# SNES_DRONE_GPIO.net
KiCad netlist of a schematic drawn in Altium Designer
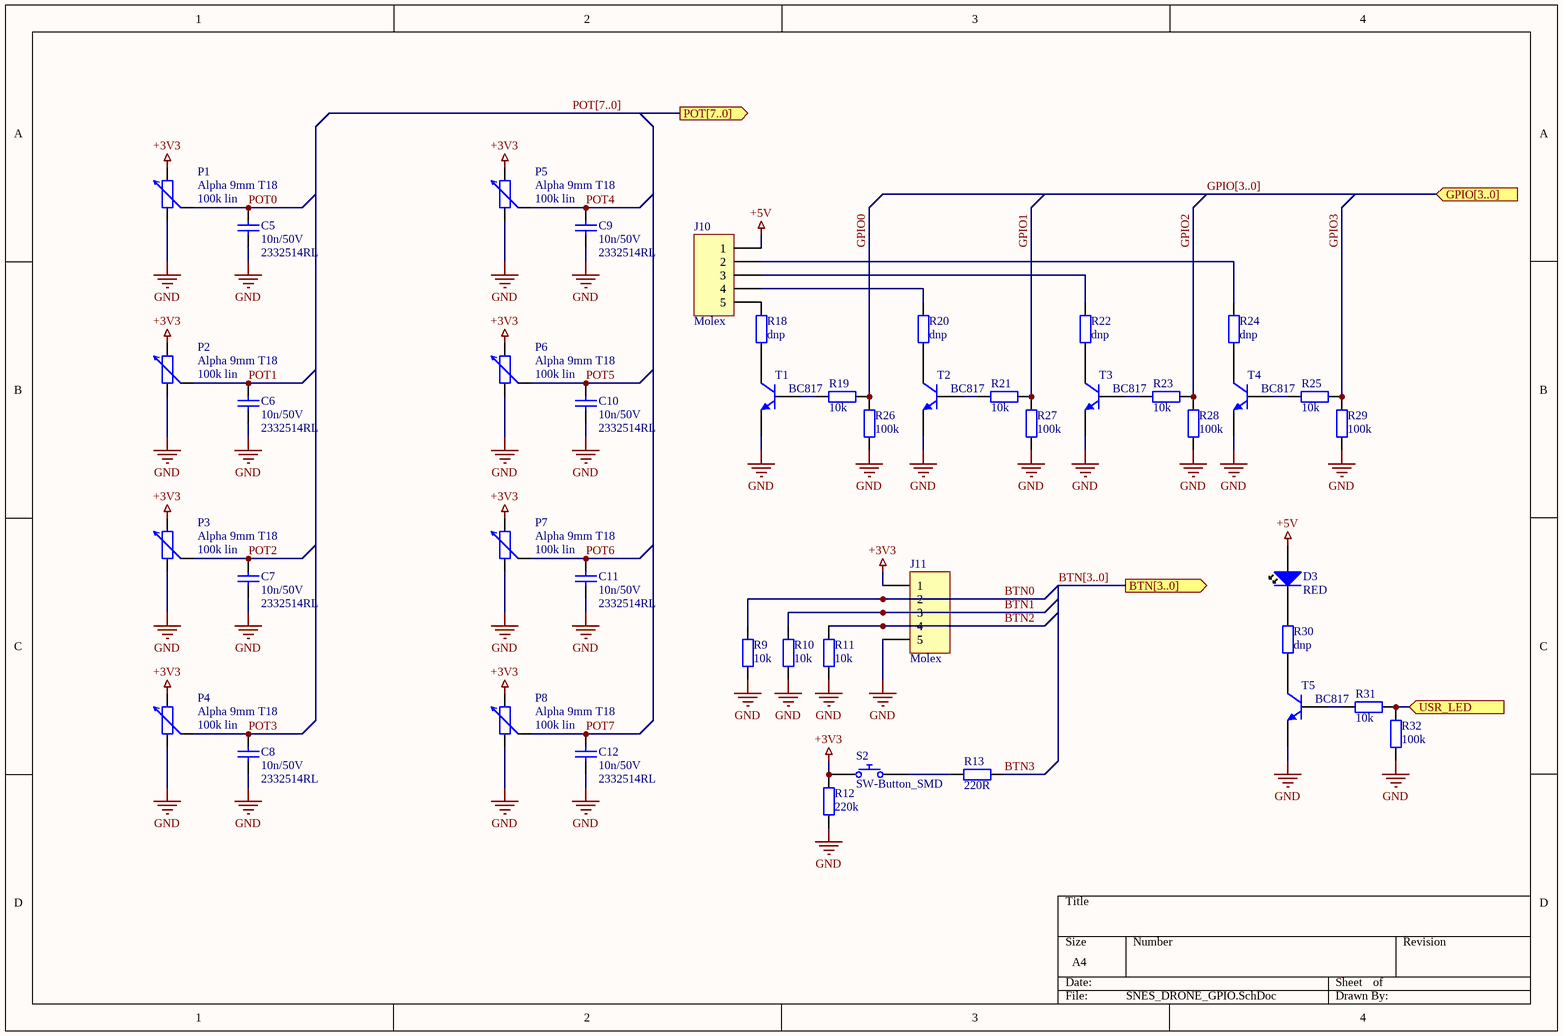
[diagram p0: SNES_DRONE_GPIO.SchDoc]

(export (version "E")
  (design (tool "Eeschema 10.0.6"))
  (components
    (comp (ref "C5")
      (value "10n/50V")
      (footprint "0402_RES")
      (fields (field (name "SUPPLIER PART NUMBER 1") "2332514RL"))
      (libsource (lib "My_Integrated_Library") (part "Cap_10n_0402"))
    )
    (comp (ref "C6")
      (value "10n/50V")
      (footprint "0402_RES")
      (fields (field (name "SUPPLIER PART NUMBER 1") "2332514RL"))
      (libsource (lib "My_Integrated_Library") (part "Cap_10n_0402"))
    )
    (comp (ref "C7")
      (value "10n/50V")
      (footprint "0402_RES")
      (fields (field (name "SUPPLIER PART NUMBER 1") "2332514RL"))
      (libsource (lib "My_Integrated_Library") (part "Cap_10n_0402"))
    )
    (comp (ref "C8")
      (value "10n/50V")
      (footprint "0402_RES")
      (fields (field (name "SUPPLIER PART NUMBER 1") "2332514RL"))
      (libsource (lib "My_Integrated_Library") (part "Cap_10n_0402"))
    )
    (comp (ref "C9")
      (value "10n/50V")
      (footprint "0402_RES")
      (fields (field (name "SUPPLIER PART NUMBER 1") "2332514RL"))
      (libsource (lib "My_Integrated_Library") (part "Cap_10n_0402"))
    )
    (comp (ref "C10")
      (value "10n/50V")
      (footprint "0402_RES")
      (fields (field (name "SUPPLIER PART NUMBER 1") "2332514RL"))
      (libsource (lib "My_Integrated_Library") (part "Cap_10n_0402"))
    )
    (comp (ref "C11")
      (value "10n/50V")
      (footprint "0402_RES")
      (fields (field (name "SUPPLIER PART NUMBER 1") "2332514RL"))
      (libsource (lib "My_Integrated_Library") (part "Cap_10n_0402"))
    )
    (comp (ref "C12")
      (value "10n/50V")
      (footprint "0402_RES")
      (fields (field (name "SUPPLIER PART NUMBER 1") "2332514RL"))
      (libsource (lib "My_Integrated_Library") (part "Cap_10n_0402"))
    )
    (comp (ref "D3")
      (value "RED")
      (footprint "0603_LED")
      (description "RED SMD 0603 LED 20mA 2V 0.04W")
      (fields (field (name "Comment") "RED LED"))
      (libsource (lib "My_Integrated_Library") (part "LED_RED_0603"))
    )
    (comp (ref "J10")
      (value "MOLEX_22-27-2051")
      (footprint "MOLEX_22-27-2051")
      (description "5 pin molex connector")
      (fields (field (name "MANUFACTURER 1") "Molex"))
      (libsource (lib "") (part "MOLEX_22-27-2051_1"))
    )
    (comp (ref "J11")
      (value "MOLEX_22-27-2051")
      (footprint "MOLEX_22-27-2051")
      (description "5 pin molex connector")
      (fields (field (name "MANUFACTURER 1") "Molex"))
      (libsource (lib "My_Integrated_Library") (part "MOLEX_22-27-2051"))
    )
    (comp (ref "P1")
      (value "100k lin")
      (footprint "ALPHA_T18")
      (description "Shaft Diameter – 6mm (0.2″)\r\nShaft Length – 15mm (0.59″)")
      (fields (field (name "NAME") "Alpha 9mm T18") (field (name "Comment") "RES_POT_100k_LIN_ALPHA_EURACK"))
      (libsource (lib "My_Integrated_Library") (part "RES_POT_100k_LIN_ALPHA_EURACK"))
    )
    (comp (ref "P2")
      (value "100k lin")
      (footprint "ALPHA_T18")
      (description "Shaft Diameter – 6mm (0.2″)\r\nShaft Length – 15mm (0.59″)")
      (fields (field (name "NAME") "Alpha 9mm T18") (field (name "Comment") "RES_POT_100k_LIN_ALPHA_EURACK"))
      (libsource (lib "My_Integrated_Library") (part "RES_POT_100k_LIN_ALPHA_EURACK"))
    )
    (comp (ref "P3")
      (value "100k lin")
      (footprint "ALPHA_T18")
      (description "Shaft Diameter – 6mm (0.2″)\r\nShaft Length – 15mm (0.59″)")
      (fields (field (name "NAME") "Alpha 9mm T18") (field (name "Comment") "RES_POT_100k_LIN_ALPHA_EURACK"))
      (libsource (lib "My_Integrated_Library") (part "RES_POT_100k_LIN_ALPHA_EURACK"))
    )
    (comp (ref "P4")
      (value "100k lin")
      (footprint "ALPHA_T18")
      (description "Shaft Diameter – 6mm (0.2″)\r\nShaft Length – 15mm (0.59″)")
      (fields (field (name "NAME") "Alpha 9mm T18") (field (name "Comment") "RES_POT_100k_LIN_ALPHA_EURACK"))
      (libsource (lib "My_Integrated_Library") (part "RES_POT_100k_LIN_ALPHA_EURACK"))
    )
    (comp (ref "P5")
      (value "100k lin")
      (footprint "ALPHA_T18")
      (description "Shaft Diameter – 6mm (0.2″)\r\nShaft Length – 15mm (0.59″)")
      (fields (field (name "NAME") "Alpha 9mm T18") (field (name "Comment") "RES_POT_100k_LIN_ALPHA_EURACK"))
      (libsource (lib "My_Integrated_Library") (part "RES_POT_100k_LIN_ALPHA_EURACK"))
    )
    (comp (ref "P6")
      (value "100k lin")
      (footprint "ALPHA_T18")
      (description "Shaft Diameter – 6mm (0.2″)\r\nShaft Length – 15mm (0.59″)")
      (fields (field (name "NAME") "Alpha 9mm T18") (field (name "Comment") "RES_POT_100k_LIN_ALPHA_EURACK"))
      (libsource (lib "My_Integrated_Library") (part "RES_POT_100k_LIN_ALPHA_EURACK"))
    )
    (comp (ref "P7")
      (value "100k lin")
      (footprint "ALPHA_T18")
      (description "Shaft Diameter – 6mm (0.2″)\r\nShaft Length – 15mm (0.59″)")
      (fields (field (name "NAME") "Alpha 9mm T18") (field (name "Comment") "RES_POT_100k_LIN_ALPHA_EURACK"))
      (libsource (lib "My_Integrated_Library") (part "RES_POT_100k_LIN_ALPHA_EURACK"))
    )
    (comp (ref "P8")
      (value "100k lin")
      (footprint "ALPHA_T18")
      (description "Shaft Diameter – 6mm (0.2″)\r\nShaft Length – 15mm (0.59″)")
      (fields (field (name "NAME") "Alpha 9mm T18") (field (name "Comment") "RES_POT_100k_LIN_ALPHA_EURACK"))
      (libsource (lib "My_Integrated_Library") (part "RES_POT_100k_LIN_ALPHA_EURACK"))
    )
    (comp (ref "R9")
      (value "10k")
      (footprint "0603_RES")
      (description "YAGEO 10kOhm 100mW ± 1%")
      (fields (field (name "Comment") "10kOhm 100mW"))
      (libsource (lib "My_Integrated_Library") (part "RES_0603_10k_100mW"))
    )
    (comp (ref "R10")
      (value "10k")
      (footprint "0603_RES")
      (description "YAGEO 10kOhm 100mW ± 1%")
      (fields (field (name "Comment") "10kOhm 100mW"))
      (libsource (lib "My_Integrated_Library") (part "RES_0603_10k_100mW"))
    )
    (comp (ref "R11")
      (value "10k")
      (footprint "0603_RES")
      (description "YAGEO 10kOhm 100mW ± 1%")
      (fields (field (name "Comment") "10kOhm 100mW"))
      (libsource (lib "My_Integrated_Library") (part "RES_0603_10k_100mW"))
    )
    (comp (ref "R12")
      (value "220k")
      (footprint "0603_RES")
      (description "VISHAY 220kOhm 100mW ± 1%")
      (fields (field (name "Comment") "220kOhm 100mW"))
      (libsource (lib "My_Integrated_Library") (part "RES_0603_220k_100mW"))
    )
    (comp (ref "R13")
      (value "220R")
      (footprint "0603_RES")
      (description "YAGEO 220Ohm 100mW ± 1%")
      (fields (field (name "Comment") "220Ohm 100mW"))
      (libsource (lib "My_Integrated_Library") (part "RES_0603_220_100mW"))
    )
    (comp (ref "R18")
      (value "dnp")
      (footprint "0603_DNP")
      (fields (field (name "Comment") "DNP"))
      (libsource (lib "My_Integrated_Library") (part "RES_DNP"))
    )
    (comp (ref "R19")
      (value "10k")
      (footprint "0603_RES")
      (description "YAGEO 10kOhm 100mW ± 1%")
      (fields (field (name "Comment") "10kOhm 100mW"))
      (libsource (lib "") (part "RES_0603_10k_100mW_1"))
    )
    (comp (ref "R20")
      (value "dnp")
      (footprint "0603_DNP")
      (fields (field (name "Comment") "DNP"))
      (libsource (lib "My_Integrated_Library") (part "RES_DNP"))
    )
    (comp (ref "R21")
      (value "10k")
      (footprint "0603_RES")
      (description "YAGEO 10kOhm 100mW ± 1%")
      (fields (field (name "Comment") "10kOhm 100mW"))
      (libsource (lib "") (part "RES_0603_10k_100mW_1"))
    )
    (comp (ref "R22")
      (value "dnp")
      (footprint "0603_DNP")
      (fields (field (name "Comment") "DNP"))
      (libsource (lib "My_Integrated_Library") (part "RES_DNP"))
    )
    (comp (ref "R23")
      (value "10k")
      (footprint "0603_RES")
      (description "YAGEO 10kOhm 100mW ± 1%")
      (fields (field (name "Comment") "10kOhm 100mW"))
      (libsource (lib "") (part "RES_0603_10k_100mW_1"))
    )
    (comp (ref "R24")
      (value "dnp")
      (footprint "0603_DNP")
      (fields (field (name "Comment") "DNP"))
      (libsource (lib "My_Integrated_Library") (part "RES_DNP"))
    )
    (comp (ref "R25")
      (value "10k")
      (footprint "0603_RES")
      (description "YAGEO 10kOhm 100mW ± 1%")
      (fields (field (name "Comment") "10kOhm 100mW"))
      (libsource (lib "") (part "RES_0603_10k_100mW_1"))
    )
    (comp (ref "R26")
      (value "100k")
      (footprint "0603_RES")
      (description "WALSIN 6.8kOhm 100mW 75 ± 1%")
      (fields (field (name "Comment") "100kOhm 100mW"))
      (libsource (lib "My_Integrated_Library") (part "RES_0603_100k_100mW"))
    )
    (comp (ref "R27")
      (value "100k")
      (footprint "0603_RES")
      (description "WALSIN 6.8kOhm 100mW 75 ± 1%")
      (fields (field (name "Comment") "100kOhm 100mW"))
      (libsource (lib "My_Integrated_Library") (part "RES_0603_100k_100mW"))
    )
    (comp (ref "R28")
      (value "100k")
      (footprint "0603_RES")
      (description "WALSIN 6.8kOhm 100mW 75 ± 1%")
      (fields (field (name "Comment") "100kOhm 100mW"))
      (libsource (lib "My_Integrated_Library") (part "RES_0603_100k_100mW"))
    )
    (comp (ref "R29")
      (value "100k")
      (footprint "0603_RES")
      (description "WALSIN 6.8kOhm 100mW 75 ± 1%")
      (fields (field (name "Comment") "100kOhm 100mW"))
      (libsource (lib "My_Integrated_Library") (part "RES_0603_100k_100mW"))
    )
    (comp (ref "R30")
      (value "dnp")
      (footprint "0603_DNP")
      (fields (field (name "Comment") "DNP"))
      (libsource (lib "My_Integrated_Library") (part "RES_DNP"))
    )
    (comp (ref "R31")
      (value "10k")
      (footprint "0603_RES")
      (description "YAGEO 10kOhm 100mW ± 1%")
      (fields (field (name "Comment") "10kOhm 100mW"))
      (libsource (lib "") (part "RES_0603_10k_100mW_1"))
    )
    (comp (ref "R32")
      (value "100k")
      (footprint "0603_RES")
      (description "WALSIN 6.8kOhm 100mW 75 ± 1%")
      (fields (field (name "Comment") "100kOhm 100mW"))
      (libsource (lib "My_Integrated_Library") (part "RES_0603_100k_100mW"))
    )
    (comp (ref "S2")
      (value "SW-Button_SMD")
      (footprint "SKQGAFE010")
      (description "ALPS SMD Push Button")
      (libsource (lib "My_Integrated_Library") (part "SW-Button_SMD"))
    )
    (comp (ref "T1")
      (value "BC817")
      (footprint "TO-236AB")
      (description "BJT, NPN, 45 V, 250 mW, 500 mA, 160 hFE")
      (libsource (lib "My_Integrated_Library") (part "BJT_NPN_BC817"))
    )
    (comp (ref "T2")
      (value "BC817")
      (footprint "TO-236AB")
      (description "BJT, NPN, 45 V, 250 mW, 500 mA, 160 hFE")
      (libsource (lib "My_Integrated_Library") (part "BJT_NPN_BC817"))
    )
    (comp (ref "T3")
      (value "BC817")
      (footprint "TO-236AB")
      (description "BJT, NPN, 45 V, 250 mW, 500 mA, 160 hFE")
      (libsource (lib "My_Integrated_Library") (part "BJT_NPN_BC817"))
    )
    (comp (ref "T4")
      (value "BC817")
      (footprint "TO-236AB")
      (description "BJT, NPN, 45 V, 250 mW, 500 mA, 160 hFE")
      (libsource (lib "My_Integrated_Library") (part "BJT_NPN_BC817"))
    )
    (comp (ref "T5")
      (value "BC817")
      (footprint "TO-236AB")
      (description "BJT, NPN, 45 V, 250 mW, 500 mA, 160 hFE")
      (libsource (lib "My_Integrated_Library") (part "BJT_NPN_BC817"))
    )
  )
  (nets
    (net (code "1") (name "+3V3") (class "Default")
      (node (ref "J11") (pin "1") (pinfunction "1_1") (pintype "passive"))
      (node (ref "P1") (pin "1") (pinfunction "1_1") (pintype "passive"))
      (node (ref "P2") (pin "1") (pinfunction "1_1") (pintype "passive"))
      (node (ref "P3") (pin "1") (pinfunction "1_1") (pintype "passive"))
      (node (ref "P4") (pin "1") (pinfunction "1_1") (pintype "passive"))
      (node (ref "P5") (pin "1") (pinfunction "1_1") (pintype "passive"))
      (node (ref "P6") (pin "1") (pinfunction "1_1") (pintype "passive"))
      (node (ref "P7") (pin "1") (pinfunction "1_1") (pintype "passive"))
      (node (ref "P8") (pin "1") (pinfunction "1_1") (pintype "passive"))
      (node (ref "R12") (pin "2") (pinfunction "2_2") (pintype "passive"))
      (node (ref "S2") (pin "3") (pinfunction "3_3") (pintype "passive"))
    )
    (net (code "2") (name "+5V") (class "Default")
      (node (ref "D3") (pin "1") (pinfunction "A_1") (pintype "passive"))
      (node (ref "J10") (pin "1") (pinfunction "1_1") (pintype "passive"))
    )
    (net (code "3") (name "/BTN0") (class "Default")
      (node (ref "J11") (pin "2") (pinfunction "2_2") (pintype "passive"))
      (node (ref "R9") (pin "2") (pinfunction "2_2") (pintype "passive"))
    )
    (net (code "4") (name "/BTN1") (class "Default")
      (node (ref "J11") (pin "3") (pinfunction "3_3") (pintype "passive"))
      (node (ref "R10") (pin "2") (pinfunction "2_2") (pintype "passive"))
    )
    (net (code "5") (name "/BTN2") (class "Default")
      (node (ref "J11") (pin "4") (pinfunction "4_4") (pintype "passive"))
      (node (ref "R11") (pin "2") (pinfunction "2_2") (pintype "passive"))
    )
    (net (code "6") (name "/BTN3") (class "Default")
      (node (ref "R13") (pin "2") (pinfunction "2_2") (pintype "passive"))
    )
    (net (code "8") (name "/GPIO0") (class "Default")
      (node (ref "R19") (pin "1") (pinfunction "1_1") (pintype "passive"))
      (node (ref "R26") (pin "2") (pinfunction "2_2") (pintype "passive"))
    )
    (net (code "9") (name "/GPIO1") (class "Default")
      (node (ref "R21") (pin "1") (pinfunction "1_1") (pintype "passive"))
      (node (ref "R27") (pin "2") (pinfunction "2_2") (pintype "passive"))
    )
    (net (code "10") (name "/GPIO2") (class "Default")
      (node (ref "R23") (pin "1") (pinfunction "1_1") (pintype "passive"))
      (node (ref "R28") (pin "2") (pinfunction "2_2") (pintype "passive"))
    )
    (net (code "11") (name "/GPIO3") (class "Default")
      (node (ref "R25") (pin "1") (pinfunction "1_1") (pintype "passive"))
      (node (ref "R29") (pin "2") (pinfunction "2_2") (pintype "passive"))
    )
    (net (code "13") (name "/POT0") (class "Default")
      (node (ref "C5") (pin "2") (pinfunction "2_2") (pintype "passive"))
      (node (ref "P1") (pin "2") (pinfunction "2_2") (pintype "passive"))
    )
    (net (code "14") (name "/POT1") (class "Default")
      (node (ref "C6") (pin "2") (pinfunction "2_2") (pintype "passive"))
      (node (ref "P2") (pin "2") (pinfunction "2_2") (pintype "passive"))
    )
    (net (code "15") (name "/POT2") (class "Default")
      (node (ref "C7") (pin "2") (pinfunction "2_2") (pintype "passive"))
      (node (ref "P3") (pin "2") (pinfunction "2_2") (pintype "passive"))
    )
    (net (code "16") (name "/POT3") (class "Default")
      (node (ref "C8") (pin "2") (pinfunction "2_2") (pintype "passive"))
      (node (ref "P4") (pin "2") (pinfunction "2_2") (pintype "passive"))
    )
    (net (code "17") (name "/POT4") (class "Default")
      (node (ref "C9") (pin "2") (pinfunction "2_2") (pintype "passive"))
      (node (ref "P5") (pin "2") (pinfunction "2_2") (pintype "passive"))
    )
    (net (code "18") (name "/POT5") (class "Default")
      (node (ref "C10") (pin "2") (pinfunction "2_2") (pintype "passive"))
      (node (ref "P6") (pin "2") (pinfunction "2_2") (pintype "passive"))
    )
    (net (code "19") (name "/POT6") (class "Default")
      (node (ref "C11") (pin "2") (pinfunction "2_2") (pintype "passive"))
      (node (ref "P7") (pin "2") (pinfunction "2_2") (pintype "passive"))
    )
    (net (code "20") (name "/POT7") (class "Default")
      (node (ref "C12") (pin "2") (pinfunction "2_2") (pintype "passive"))
      (node (ref "P8") (pin "2") (pinfunction "2_2") (pintype "passive"))
    )
    (net (code "22") (name "/USR_LED") (class "Default")
      (node (ref "R31") (pin "1") (pinfunction "1_1") (pintype "passive"))
      (node (ref "R32") (pin "2") (pinfunction "2_2") (pintype "passive"))
    )
    (net (code "23") (name "GND") (class "Default")
      (node (ref "C10") (pin "1") (pinfunction "1_1") (pintype "passive"))
      (node (ref "C11") (pin "1") (pinfunction "1_1") (pintype "passive"))
      (node (ref "C12") (pin "1") (pinfunction "1_1") (pintype "passive"))
      (node (ref "C5") (pin "1") (pinfunction "1_1") (pintype "passive"))
      (node (ref "C6") (pin "1") (pinfunction "1_1") (pintype "passive"))
      (node (ref "C7") (pin "1") (pinfunction "1_1") (pintype "passive"))
      (node (ref "C8") (pin "1") (pinfunction "1_1") (pintype "passive"))
      (node (ref "C9") (pin "1") (pinfunction "1_1") (pintype "passive"))
      (node (ref "J11") (pin "5") (pinfunction "5_5") (pintype "passive"))
      (node (ref "P1") (pin "3") (pinfunction "3_3") (pintype "passive"))
      (node (ref "P2") (pin "3") (pinfunction "3_3") (pintype "passive"))
      (node (ref "P3") (pin "3") (pinfunction "3_3") (pintype "passive"))
      (node (ref "P4") (pin "3") (pinfunction "3_3") (pintype "passive"))
      (node (ref "P5") (pin "3") (pinfunction "3_3") (pintype "passive"))
      (node (ref "P6") (pin "3") (pinfunction "3_3") (pintype "passive"))
      (node (ref "P7") (pin "3") (pinfunction "3_3") (pintype "passive"))
      (node (ref "P8") (pin "3") (pinfunction "3_3") (pintype "passive"))
      (node (ref "R10") (pin "1") (pinfunction "1_1") (pintype "passive"))
      (node (ref "R11") (pin "1") (pinfunction "1_1") (pintype "passive"))
      (node (ref "R12") (pin "1") (pinfunction "1_1") (pintype "passive"))
      (node (ref "R26") (pin "1") (pinfunction "1_1") (pintype "passive"))
      (node (ref "R27") (pin "1") (pinfunction "1_1") (pintype "passive"))
      (node (ref "R28") (pin "1") (pinfunction "1_1") (pintype "passive"))
      (node (ref "R29") (pin "1") (pinfunction "1_1") (pintype "passive"))
      (node (ref "R32") (pin "1") (pinfunction "1_1") (pintype "passive"))
      (node (ref "R9") (pin "1") (pinfunction "1_1") (pintype "passive"))
      (node (ref "T1") (pin "2") (pinfunction "2_2") (pintype "passive"))
      (node (ref "T2") (pin "2") (pinfunction "2_2") (pintype "passive"))
      (node (ref "T3") (pin "2") (pinfunction "2_2") (pintype "passive"))
      (node (ref "T4") (pin "2") (pinfunction "2_2") (pintype "passive"))
      (node (ref "T5") (pin "2") (pinfunction "2_2") (pintype "passive"))
    )
    (net (code "24") (name "Net-(D3-K)") (class "Default")
      (node (ref "D3") (pin "2") (pinfunction "K_2") (pintype "passive"))
      (node (ref "R30") (pin "2") (pinfunction "2_2") (pintype "passive"))
    )
    (net (code "25") (name "Net-(J10-Pad2)") (class "Default")
      (node (ref "J10") (pin "2") (pinfunction "2_2") (pintype "passive"))
      (node (ref "R24") (pin "2") (pinfunction "2_2") (pintype "passive"))
    )
    (net (code "26") (name "Net-(J10-Pad3)") (class "Default")
      (node (ref "J10") (pin "3") (pinfunction "3_3") (pintype "passive"))
      (node (ref "R22") (pin "2") (pinfunction "2_2") (pintype "passive"))
    )
    (net (code "27") (name "Net-(J10-Pad4)") (class "Default")
      (node (ref "J10") (pin "4") (pinfunction "4_4") (pintype "passive"))
      (node (ref "R20") (pin "2") (pinfunction "2_2") (pintype "passive"))
    )
    (net (code "28") (name "Net-(J10-Pad5)") (class "Default")
      (node (ref "J10") (pin "5") (pinfunction "5_5") (pintype "passive"))
      (node (ref "R18") (pin "2") (pinfunction "2_2") (pintype "passive"))
    )
    (net (code "29") (name "Net-(R13-Pad1)") (class "Default")
      (node (ref "R13") (pin "1") (pinfunction "1_1") (pintype "passive"))
      (node (ref "S2") (pin "1") (pinfunction "1_1") (pintype "passive"))
    )
    (net (code "30") (name "Net-(R18-Pad1)") (class "Default")
      (node (ref "R18") (pin "1") (pinfunction "1_1") (pintype "passive"))
      (node (ref "T1") (pin "3") (pinfunction "3_3") (pintype "passive"))
    )
    (net (code "31") (name "Net-(R19-Pad2)") (class "Default")
      (node (ref "R19") (pin "2") (pinfunction "2_2") (pintype "passive"))
      (node (ref "T1") (pin "1") (pinfunction "1_1") (pintype "passive"))
    )
    (net (code "32") (name "Net-(R20-Pad1)") (class "Default")
      (node (ref "R20") (pin "1") (pinfunction "1_1") (pintype "passive"))
      (node (ref "T2") (pin "3") (pinfunction "3_3") (pintype "passive"))
    )
    (net (code "33") (name "Net-(R21-Pad2)") (class "Default")
      (node (ref "R21") (pin "2") (pinfunction "2_2") (pintype "passive"))
      (node (ref "T2") (pin "1") (pinfunction "1_1") (pintype "passive"))
    )
    (net (code "34") (name "Net-(R22-Pad1)") (class "Default")
      (node (ref "R22") (pin "1") (pinfunction "1_1") (pintype "passive"))
      (node (ref "T3") (pin "3") (pinfunction "3_3") (pintype "passive"))
    )
    (net (code "35") (name "Net-(R23-Pad2)") (class "Default")
      (node (ref "R23") (pin "2") (pinfunction "2_2") (pintype "passive"))
      (node (ref "T3") (pin "1") (pinfunction "1_1") (pintype "passive"))
    )
    (net (code "36") (name "Net-(R24-Pad1)") (class "Default")
      (node (ref "R24") (pin "1") (pinfunction "1_1") (pintype "passive"))
      (node (ref "T4") (pin "3") (pinfunction "3_3") (pintype "passive"))
    )
    (net (code "37") (name "Net-(R25-Pad2)") (class "Default")
      (node (ref "R25") (pin "2") (pinfunction "2_2") (pintype "passive"))
      (node (ref "T4") (pin "1") (pinfunction "1_1") (pintype "passive"))
    )
    (net (code "38") (name "Net-(R30-Pad1)") (class "Default")
      (node (ref "R30") (pin "1") (pinfunction "1_1") (pintype "passive"))
      (node (ref "T5") (pin "3") (pinfunction "3_3") (pintype "passive"))
    )
    (net (code "39") (name "Net-(R31-Pad2)") (class "Default")
      (node (ref "R31") (pin "2") (pinfunction "2_2") (pintype "passive"))
      (node (ref "T5") (pin "1") (pinfunction "1_1") (pintype "passive"))
    )
  )
)
